# RecoveryBoard_V3.net
KiCad netlist of a schematic drawn in Altium Designer
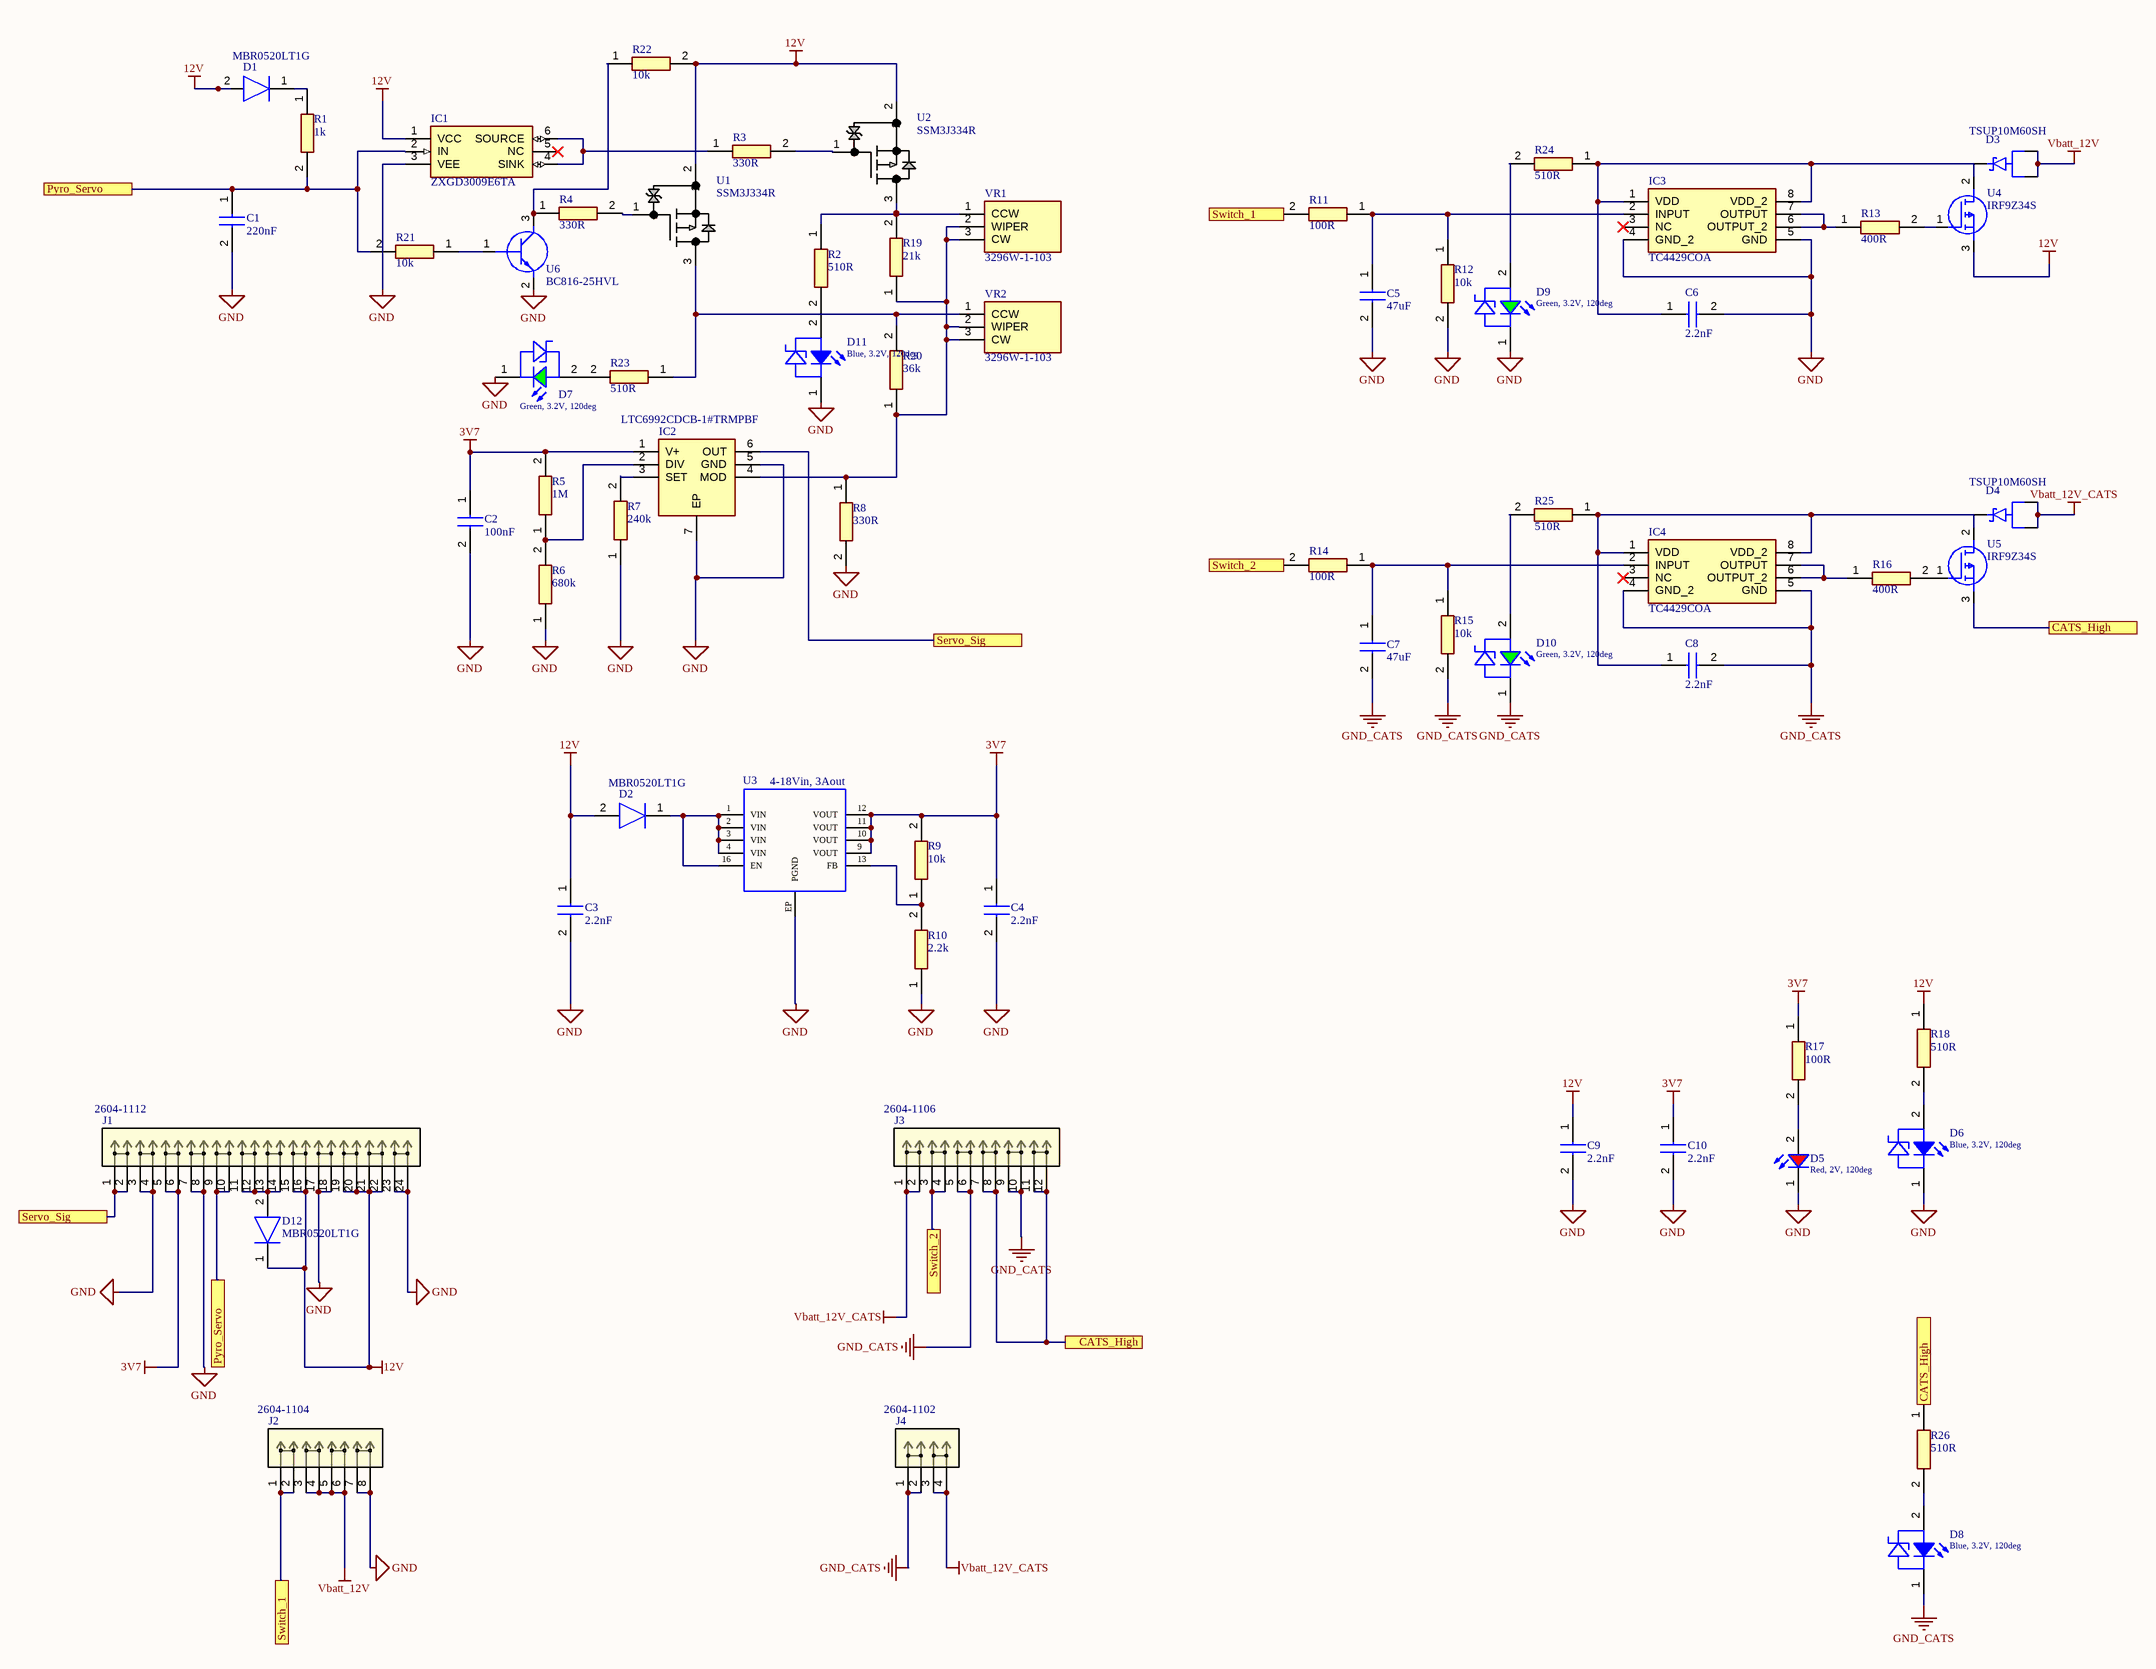
[diagram p0: RecoveryBoard_V3.SchDoc]

(export (version "E")
  (design (tool "Eeschema 10.0.6"))
  (components
    (comp (ref "C1")
      (value "220nF")
      (footprint "SamacSys:CAPC1608X87N")
      (description "Capacitor")
      (fields (field (name "MANUFACTURER_PART_NUMBER") "885012206036"))
      (libsource (lib "SamacSys") (part "885012206036"))
    )
    (comp (ref "C2")
      (value "100nF")
      (footprint "SamacSys:CAPC1608X87N")
      (description "Capacitor")
      (fields (field (name "MANUFACTURER_PART_NUMBER") "885012206036"))
      (libsource (lib "SamacSys") (part "885012206036"))
    )
    (comp (ref "C3")
      (value "2.2nF")
      (footprint "SamacSys:CAPC1608X87N")
      (description "Capacitor")
      (fields (field (name "MANUFACTURER_PART_NUMBER") "885012206036"))
      (libsource (lib "SamacSys") (part "885012206036"))
    )
    (comp (ref "C4")
      (value "2.2nF")
      (footprint "SamacSys:CAPC1608X87N")
      (description "Capacitor")
      (fields (field (name "MANUFACTURER_PART_NUMBER") "885012206036"))
      (libsource (lib "SamacSys") (part "885012206036"))
    )
    (comp (ref "C5")
      (value "47uF")
      (footprint "SamacSys:CAPC1608X87N")
      (description "Capacitor")
      (fields (field (name "MANUFACTURER_PART_NUMBER") "885012206036"))
      (libsource (lib "SamacSys") (part "885012206036"))
    )
    (comp (ref "C6")
      (value "2.2nF")
      (footprint "SamacSys:CAPC1608X87N")
      (description "Capacitor")
      (fields (field (name "MANUFACTURER_PART_NUMBER") "885012206036"))
      (libsource (lib "SamacSys") (part "885012206036"))
    )
    (comp (ref "C7")
      (value "47uF")
      (footprint "SamacSys:CAPC1608X87N")
      (description "Capacitor")
      (fields (field (name "MANUFACTURER_PART_NUMBER") "885012206036"))
      (libsource (lib "SamacSys") (part "885012206036"))
    )
    (comp (ref "C8")
      (value "2.2nF")
      (footprint "SamacSys:CAPC1608X87N")
      (description "Capacitor")
      (fields (field (name "MANUFACTURER_PART_NUMBER") "885012206036"))
      (libsource (lib "SamacSys") (part "885012206036"))
    )
    (comp (ref "C9")
      (value "2.2nF")
      (footprint "SamacSys:CAPC1608X87N")
      (description "Capacitor")
      (fields (field (name "MANUFACTURER_PART_NUMBER") "885012206036"))
      (libsource (lib "SamacSys") (part "885012206036"))
    )
    (comp (ref "C10")
      (value "2.2nF")
      (footprint "SamacSys:CAPC1608X87N")
      (description "Capacitor")
      (fields (field (name "MANUFACTURER_PART_NUMBER") "885012206036"))
      (libsource (lib "SamacSys") (part "885012206036"))
    )
    (comp (ref "D1")
      (value "MBR0520LT1G")
      (footprint "SamacSys:SOD3716X135N")
      (description "Diode")
      (libsource (lib "SamacSys") (part "MBR0520LT1G"))
    )
    (comp (ref "D2")
      (value "MBR0520LT1G")
      (footprint "SamacSys:SOD3716X135N")
      (description "Diode")
      (libsource (lib "SamacSys") (part "MBR0520LT1G"))
    )
    (comp (ref "D3")
      (value "TSUP10M60SH")
      (footprint "DIO_TSUP10M60SH")
      (libsource (lib "TSUP10M60SH") (part "TSUP10M60SH"))
    )
    (comp (ref "D4")
      (value "TSUP10M60SH")
      (footprint "DIO_TSUP10M60SH")
      (libsource (lib "TSUP10M60SH") (part "TSUP10M60SH"))
    )
    (comp (ref "D5")
      (value "Red, 2V, 120deg")
      (footprint "WL-SMCC_0603_RS_VS_YS")
      (description "WL-SMCC SMD Mono-color Chip LED Compact, size 0603, Red, 2V, 120deg")
      (fields (field (name "PART NUMBER") "150060RS73220") (field (name "PUBLISHER") "Wurth Elektronik"))
      (libsource (lib "Altium_WL-SMCC (rev19a)") (part "150060RS73220"))
    )
    (comp (ref "D6")
      (value "Blue, 3.2V, 120deg")
      (footprint "WL-SMCC_0603_GS_BS")
      (description "WL-SMCC SMD Mono-color Chip LED Compact, size 0603, Blue, 3.2V, 120deg")
      (fields (field (name "PART NUMBER") "150060BS73220") (field (name "PUBLISHER") "Wurth Elektronik"))
      (libsource (lib "Altium_WL-SMCC (rev19a)") (part "150060BS73220"))
    )
    (comp (ref "D7")
      (value "Green, 3.2V, 120deg")
      (footprint "WL-SMCC_0603_GS_BS")
      (description "WL-SMCC SMD Mono-color Chip LED Compact, size 0603, Green, 3.2V, 120deg")
      (fields (field (name "PART NUMBER") "150060GS73220") (field (name "PUBLISHER") "Wurth Elektronik"))
      (libsource (lib "Altium_WL-SMCC (rev19a)") (part "150060GS73220"))
    )
    (comp (ref "D8")
      (value "Blue, 3.2V, 120deg")
      (footprint "WL-SMCC_0603_GS_BS")
      (description "WL-SMCC SMD Mono-color Chip LED Compact, size 0603, Blue, 3.2V, 120deg")
      (fields (field (name "PART NUMBER") "150060BS73220") (field (name "PUBLISHER") "Wurth Elektronik"))
      (libsource (lib "Altium_WL-SMCC (rev19a)") (part "150060BS73220"))
    )
    (comp (ref "D9")
      (value "Green, 3.2V, 120deg")
      (footprint "WL-SMCC_0603_GS_BS")
      (description "WL-SMCC SMD Mono-color Chip LED Compact, size 0603, Green, 3.2V, 120deg")
      (fields (field (name "PART NUMBER") "150060GS73220") (field (name "PUBLISHER") "Wurth Elektronik"))
      (libsource (lib "Altium_WL-SMCC (rev19a)") (part "150060GS73220"))
    )
    (comp (ref "D10")
      (value "Green, 3.2V, 120deg")
      (footprint "WL-SMCC_0603_GS_BS")
      (description "WL-SMCC SMD Mono-color Chip LED Compact, size 0603, Green, 3.2V, 120deg")
      (fields (field (name "PART NUMBER") "150060GS73220") (field (name "PUBLISHER") "Wurth Elektronik"))
      (libsource (lib "Altium_WL-SMCC (rev19a)") (part "150060GS73220"))
    )
    (comp (ref "D11")
      (value "Blue, 3.2V, 120deg")
      (footprint "WL-SMCC_0603_GS_BS")
      (description "WL-SMCC SMD Mono-color Chip LED Compact, size 0603, Blue, 3.2V, 120deg")
      (fields (field (name "PART NUMBER") "150060BS73220") (field (name "PUBLISHER") "Wurth Elektronik"))
      (libsource (lib "Altium_WL-SMCC (rev19a)") (part "150060BS73220"))
    )
    (comp (ref "D12")
      (value "MBR0520LT1G")
      (footprint "SamacSys:SOD3716X135N")
      (description "Diode")
      (libsource (lib "SamacSys") (part "MBR0520LT1G"))
    )
    (comp (ref "IC1")
      (value "ZXGD3009E6TA")
      (footprint "SamacSys:SOT95P285X140-6N")
      (description "Integrated Circuit")
      (fields (field (name "MOUSER2 PART NUMBER") "621-ZXGD3009E6TA"))
      (libsource (lib "SamacSys") (part "ZXGD3009E6TA"))
    )
    (comp (ref "IC2")
      (value "LTC6992CDCB-1#TRMPBF")
      (footprint "SamacSys:SON50P300X200X80-7N-D")
      (description "Integrated Circuit")
      (libsource (lib "SamacSys") (part "LTC6992CDCB-1#TRMPBF"))
    )
    (comp (ref "IC3")
      (value "TC4429COA")
      (footprint "SamacSys:SOIC127P600X175-8N")
      (description "Integrated Circuit")
      (fields (field (name "MOUSER2 PART NUMBER") "579-TC4429COA"))
      (libsource (lib "SamacSys") (part "TC4429COA"))
    )
    (comp (ref "IC4")
      (value "TC4429COA")
      (footprint "SamacSys:SOIC127P600X175-8N")
      (description "Integrated Circuit")
      (fields (field (name "MOUSER2 PART NUMBER") "579-TC4429COA"))
      (libsource (lib "SamacSys") (part "TC4429COA"))
    )
    (comp (ref "J1")
      (value "2604-1112")
      (footprint "CONN_2604-1112_24_WAG")
      (description "No Description Available")
      (fields (field (name "COPYRIGHT") "Copyright (C) 2022 Ultra Librarian. All rights reserved."))
      (libsource (lib "2604-1112") (part "2604-1112"))
    )
    (comp (ref "J2")
      (value "2604-1104")
      (footprint "CONN_2604-1104_8_WAG")
      (description "No Description Available")
      (fields (field (name "COPYRIGHT") "Copyright (C) 2022 Ultra Librarian. All rights reserved."))
      (libsource (lib "2604-1104") (part "2604-1104"))
    )
    (comp (ref "J3")
      (value "2604-1106")
      (footprint "CONN_2604-1106_12_WAG")
      (description "No Description Available")
      (fields (field (name "COPYRIGHT") "Copyright (C) 2022 Ultra Librarian. All rights reserved."))
      (libsource (lib "2604-1106") (part "2604-1106"))
    )
    (comp (ref "J4")
      (value "2604-1102")
      (footprint "CONN_2604-1102_4_WAG")
      (description "No Description Available")
      (fields (field (name "COPYRIGHT") "Copyright (C) 2022 Ultra Librarian. All rights reserved."))
      (libsource (lib "2604-1102") (part "2604-1102"))
    )
    (comp (ref "R1")
      (value "1k")
      (footprint "SamacSys:RESC1608X55N")
      (description "Resistor")
      (fields (field (name "MANUFACTURER_PART_NUMBER") "SDR03EZPF1003"))
      (libsource (lib "") (part "SDR03EZPF1003_3"))
    )
    (comp (ref "R2")
      (value "510R")
      (footprint "SamacSys:RESC1608X55N")
      (description "Resistor")
      (fields (field (name "MANUFACTURER_PART_NUMBER") "SDR03EZPF1003"))
      (libsource (lib "") (part "SDR03EZPF1003_3"))
    )
    (comp (ref "R3")
      (value "330R")
      (footprint "SamacSys:RESC1608X55N")
      (description "Resistor")
      (fields (field (name "MANUFACTURER_PART_NUMBER") "SDR03EZPF1003"))
      (libsource (lib "SamacSys") (part "SDR03EZPF1003"))
    )
    (comp (ref "R4")
      (value "330R")
      (footprint "SamacSys:RESC1608X55N")
      (description "Resistor")
      (fields (field (name "MANUFACTURER_PART_NUMBER") "SDR03EZPF1003"))
      (libsource (lib "SamacSys") (part "SDR03EZPF1003"))
    )
    (comp (ref "R5")
      (value "1M")
      (footprint "SamacSys:RESC1608X55N")
      (description "Resistor")
      (fields (field (name "MANUFACTURER_PART_NUMBER") "SDR03EZPF1003"))
      (libsource (lib "") (part "SDR03EZPF1003_2"))
    )
    (comp (ref "R6")
      (value "680k")
      (footprint "SamacSys:RESC1608X55N")
      (description "Resistor")
      (fields (field (name "MANUFACTURER_PART_NUMBER") "SDR03EZPF1003"))
      (libsource (lib "") (part "SDR03EZPF1003_2"))
    )
    (comp (ref "R7")
      (value "240k")
      (footprint "SamacSys:RESC1608X55N")
      (description "Resistor")
      (fields (field (name "MANUFACTURER_PART_NUMBER") "SDR03EZPF1003"))
      (libsource (lib "") (part "SDR03EZPF1003_2"))
    )
    (comp (ref "R8")
      (value "330R")
      (footprint "SamacSys:RESC1608X55N")
      (description "Resistor")
      (fields (field (name "MANUFACTURER_PART_NUMBER") "SDR03EZPF1003"))
      (libsource (lib "") (part "SDR03EZPF1003_3"))
    )
    (comp (ref "R9")
      (value "10k")
      (footprint "SamacSys:RESC1608X55N")
      (description "Resistor")
      (fields (field (name "MANUFACTURER_PART_NUMBER") "SDR03EZPF1003"))
      (libsource (lib "") (part "SDR03EZPF1003_2"))
    )
    (comp (ref "R10")
      (value "2.2k")
      (footprint "SamacSys:RESC1608X55N")
      (description "Resistor")
      (fields (field (name "MANUFACTURER_PART_NUMBER") "SDR03EZPF1003"))
      (libsource (lib "") (part "SDR03EZPF1003_2"))
    )
    (comp (ref "R11")
      (value "100R")
      (footprint "SamacSys:RESC1608X55N")
      (description "Resistor")
      (fields (field (name "MANUFACTURER_PART_NUMBER") "SDR03EZPF1003"))
      (libsource (lib "") (part "SDR03EZPF1003_1"))
    )
    (comp (ref "R12")
      (value "10k")
      (footprint "SamacSys:RESC1608X55N")
      (description "Resistor")
      (fields (field (name "MANUFACTURER_PART_NUMBER") "SDR03EZPF1003"))
      (libsource (lib "") (part "SDR03EZPF1003_3"))
    )
    (comp (ref "R13")
      (value "400R")
      (footprint "SamacSys:RESC1608X55N")
      (description "Resistor")
      (fields (field (name "MANUFACTURER_PART_NUMBER") "SDR03EZPF1003"))
      (libsource (lib "SamacSys") (part "SDR03EZPF1003"))
    )
    (comp (ref "R14")
      (value "100R")
      (footprint "SamacSys:RESC1608X55N")
      (description "Resistor")
      (fields (field (name "MANUFACTURER_PART_NUMBER") "SDR03EZPF1003"))
      (libsource (lib "") (part "SDR03EZPF1003_1"))
    )
    (comp (ref "R15")
      (value "10k")
      (footprint "SamacSys:RESC1608X55N")
      (description "Resistor")
      (fields (field (name "MANUFACTURER_PART_NUMBER") "SDR03EZPF1003"))
      (libsource (lib "") (part "SDR03EZPF1003_3"))
    )
    (comp (ref "R16")
      (value "400R")
      (footprint "SamacSys:RESC1608X55N")
      (description "Resistor")
      (fields (field (name "MANUFACTURER_PART_NUMBER") "SDR03EZPF1003"))
      (libsource (lib "SamacSys") (part "SDR03EZPF1003"))
    )
    (comp (ref "R17")
      (value "100R")
      (footprint "SamacSys:RESC1608X55N")
      (description "Resistor")
      (fields (field (name "MANUFACTURER_PART_NUMBER") "SDR03EZPF1003"))
      (libsource (lib "") (part "SDR03EZPF1003_3"))
    )
    (comp (ref "R18")
      (value "510R")
      (footprint "SamacSys:RESC1608X55N")
      (description "Resistor")
      (fields (field (name "MANUFACTURER_PART_NUMBER") "SDR03EZPF1003"))
      (libsource (lib "") (part "SDR03EZPF1003_3"))
    )
    (comp (ref "R19")
      (value "21k")
      (footprint "SamacSys:RESC1608X55N")
      (description "Resistor")
      (fields (field (name "MANUFACTURER_PART_NUMBER") "SDR03EZPF1003"))
      (libsource (lib "") (part "SDR03EZPF1003_2"))
    )
    (comp (ref "R20")
      (value "36k")
      (footprint "SamacSys:RESC1608X55N")
      (description "Resistor")
      (fields (field (name "MANUFACTURER_PART_NUMBER") "SDR03EZPF1003"))
      (libsource (lib "") (part "SDR03EZPF1003_2"))
    )
    (comp (ref "R21")
      (value "10k")
      (footprint "SamacSys:RESC1608X55N")
      (description "Resistor")
      (fields (field (name "MANUFACTURER_PART_NUMBER") "SDR03EZPF1003"))
      (libsource (lib "") (part "SDR03EZPF1003_1"))
    )
    (comp (ref "R22")
      (value "10k")
      (footprint "SamacSys:RESC1608X55N")
      (description "Resistor")
      (fields (field (name "MANUFACTURER_PART_NUMBER") "SDR03EZPF1003"))
      (libsource (lib "SamacSys") (part "SDR03EZPF1003"))
    )
    (comp (ref "R23")
      (value "510R")
      (footprint "SamacSys:RESC1608X55N")
      (description "Resistor")
      (fields (field (name "MANUFACTURER_PART_NUMBER") "SDR03EZPF1003"))
      (libsource (lib "") (part "SDR03EZPF1003_1"))
    )
    (comp (ref "R24")
      (value "510R")
      (footprint "SamacSys:RESC1608X55N")
      (description "Resistor")
      (fields (field (name "MANUFACTURER_PART_NUMBER") "SDR03EZPF1003"))
      (libsource (lib "") (part "SDR03EZPF1003_1"))
    )
    (comp (ref "R25")
      (value "510R")
      (footprint "SamacSys:RESC1608X55N")
      (description "Resistor")
      (fields (field (name "MANUFACTURER_PART_NUMBER") "SDR03EZPF1003"))
      (libsource (lib "") (part "SDR03EZPF1003_1"))
    )
    (comp (ref "R26")
      (value "510R")
      (footprint "SamacSys:RESC1608X55N")
      (description "Resistor")
      (fields (field (name "MANUFACTURER_PART_NUMBER") "SDR03EZPF1003"))
      (libsource (lib "") (part "SDR03EZPF1003_3"))
    )
    (comp (ref "U1")
      (value "SSM3J334R")
      (footprint "SOT-23F_TOS")
      (description "No Description Available")
      (fields (field (name "COPYRIGHT") "Copyright (C) 2022 Ultra Librarian. All rights reserved."))
      (libsource (lib "SSM3J334R") (part "SSM3J334R"))
    )
    (comp (ref "U2")
      (value "SSM3J334R")
      (footprint "SOT-23F_TOS")
      (description "No Description Available")
      (fields (field (name "COPYRIGHT") "Copyright (C) 2022 Ultra Librarian. All rights reserved."))
      (libsource (lib "SSM3J334R") (part "SSM3J334R"))
    )
    (comp (ref "U3")
      (value "4-18Vin, 3Aout")
      (footprint "LGA-16EP")
      (description "MagI3C-VDRM Variable Step Down Regulator Module, LGA-16EP, 4-18Vin, 3Aout")
      (fields
        (field (name "MANUFACTURER PART NUMBER") "171031801")
        (field (name "MANUFACTURER") "Wurth Elektronik")
      )
      (libsource (lib "MagIC-VDRM (rev20a)") (part "171031801"))
    )
    (comp (ref "U4")
      (value "IRF9Z34S")
      (footprint "SamacSys:TO-263(D2PAK)")
      (description "MOSFET (P-Channel)")
      (fields (field (name "MOUSER PART NUMBER") "844-IRF9Z34S"))
      (libsource (lib "SamacSys") (part "IRF9Z34S"))
    )
    (comp (ref "U5")
      (value "IRF9Z34S")
      (footprint "SamacSys:TO-263(D2PAK)")
      (description "MOSFET (P-Channel)")
      (fields (field (name "MOUSER PART NUMBER") "844-IRF9Z34S"))
      (libsource (lib "SamacSys") (part "IRF9Z34S"))
    )
    (comp (ref "U6")
      (value "BC816-25HVL")
      (footprint "SamacSys:SOT95P230X110-3N")
      (description "Transistor BJT NPN")
      (libsource (lib "*") (part "BC816-25HVL"))
    )
    (comp (ref "VR1")
      (value "3296W-1-103")
      (footprint "SamacSys:3296W1103")
      (description "Variable Resistor")
      (fields (field (name "MOUSER PART NUMBER") "652-3296W-1-103"))
      (libsource (lib "SamacSys") (part "3296W-1-103"))
    )
    (comp (ref "VR2")
      (value "3296W-1-103")
      (footprint "SamacSys:3296W1103")
      (description "Variable Resistor")
      (fields (field (name "MOUSER PART NUMBER") "652-3296W-1-103"))
      (libsource (lib "SamacSys") (part "3296W-1-103"))
    )
  )
  (nets
    (net (code "1") (name "/CATS_High") (class "Default")
      (node (ref "J3") (pin "11") (pinfunction "11_11") (pintype "passive"))
      (node (ref "J3") (pin "12") (pinfunction "12_12") (pintype "passive"))
      (node (ref "J3") (pin "7") (pinfunction "7_7") (pintype "passive"))
      (node (ref "J3") (pin "8") (pinfunction "8_8") (pintype "passive"))
      (node (ref "R26") (pin "1") (pinfunction "1_1") (pintype "passive"))
      (node (ref "U5") (pin "3") (pinfunction "G_3") (pintype "passive"))
    )
    (net (code "2") (name "/Pyro_Servo") (class "Default")
      (node (ref "C1") (pin "1") (pinfunction "1_1") (pintype "passive"))
      (node (ref "IC1") (pin "2") (pinfunction "IN_2") (pintype "input"))
      (node (ref "J1") (pin "10") (pinfunction "10_10") (pintype "passive"))
      (node (ref "J1") (pin "9") (pinfunction "9_9") (pintype "passive"))
      (node (ref "R1") (pin "2") (pinfunction "2_2") (pintype "passive"))
      (node (ref "R21") (pin "2") (pinfunction "2_2") (pintype "passive"))
    )
    (net (code "3") (name "/Servo_Sig") (class "Default")
      (node (ref "IC2") (pin "6") (pinfunction "OUT_6") (pintype "passive"))
      (node (ref "J1") (pin "1") (pinfunction "1_1") (pintype "passive"))
      (node (ref "J1") (pin "2") (pinfunction "2_2") (pintype "passive"))
    )
    (net (code "4") (name "/Switch_1") (class "Default")
      (node (ref "J2") (pin "1") (pinfunction "1_1") (pintype "passive"))
      (node (ref "J2") (pin "2") (pinfunction "2_2") (pintype "passive"))
      (node (ref "R11") (pin "2") (pinfunction "2_2") (pintype "passive"))
    )
    (net (code "5") (name "/Switch_2") (class "Default")
      (node (ref "J3") (pin "3") (pinfunction "3_3") (pintype "passive"))
      (node (ref "J3") (pin "4") (pinfunction "4_4") (pintype "passive"))
      (node (ref "R14") (pin "2") (pinfunction "2_2") (pintype "passive"))
    )
    (net (code "6") (name "3V7") (class "Default")
      (node (ref "C10") (pin "1") (pinfunction "1_1") (pintype "passive"))
      (node (ref "C2") (pin "1") (pinfunction "1_1") (pintype "passive"))
      (node (ref "C4") (pin "1") (pinfunction "1_1") (pintype "passive"))
      (node (ref "IC2") (pin "1") (pinfunction "V+_1") (pintype "passive"))
      (node (ref "J1") (pin "5") (pinfunction "5_5") (pintype "passive"))
      (node (ref "J1") (pin "6") (pinfunction "6_6") (pintype "passive"))
      (node (ref "R17") (pin "1") (pinfunction "1_1") (pintype "passive"))
      (node (ref "R5") (pin "2") (pinfunction "2_2") (pintype "passive"))
      (node (ref "R9") (pin "2") (pinfunction "2_2") (pintype "passive"))
      (node (ref "U3") (pin "10") (pinfunction "VOUT_10") (pintype "passive"))
      (node (ref "U3") (pin "11") (pinfunction "VOUT_11") (pintype "passive"))
      (node (ref "U3") (pin "12") (pinfunction "VOUT_12") (pintype "passive"))
      (node (ref "U3") (pin "9") (pinfunction "VOUT_9") (pintype "passive"))
    )
    (net (code "7") (name "12V") (class "Default")
      (node (ref "C3") (pin "1") (pinfunction "1_1") (pintype "passive"))
      (node (ref "C9") (pin "1") (pinfunction "1_1") (pintype "passive"))
      (node (ref "D1") (pin "2") (pinfunction "A_2") (pintype "passive"))
      (node (ref "D12") (pin "1") (pinfunction "K_1") (pintype "passive"))
      (node (ref "D2") (pin "2") (pinfunction "A_2") (pintype "passive"))
      (node (ref "IC1") (pin "1") (pinfunction "VCC_1") (pintype "power_in"))
      (node (ref "J1") (pin "15") (pinfunction "15_15") (pintype "passive"))
      (node (ref "J1") (pin "16") (pinfunction "16_16") (pintype "passive"))
      (node (ref "J1") (pin "19") (pinfunction "19_19") (pintype "passive"))
      (node (ref "J1") (pin "20") (pinfunction "20_20") (pintype "passive"))
      (node (ref "J1") (pin "21") (pinfunction "21_21") (pintype "passive"))
      (node (ref "J1") (pin "22") (pinfunction "22_22") (pintype "passive"))
      (node (ref "R18") (pin "1") (pinfunction "1_1") (pintype "passive"))
      (node (ref "R22") (pin "2") (pinfunction "2_2") (pintype "passive"))
      (node (ref "U1") (pin "2") (pinfunction "2_2") (pintype "passive"))
      (node (ref "U2") (pin "2") (pinfunction "2_2") (pintype "passive"))
      (node (ref "U4") (pin "3") (pinfunction "G_3") (pintype "passive"))
    )
    (net (code "8") (name "GND") (class "Default")
      (node (ref "C1") (pin "2") (pinfunction "2_2") (pintype "passive"))
      (node (ref "C10") (pin "2") (pinfunction "2_2") (pintype "passive"))
      (node (ref "C2") (pin "2") (pinfunction "2_2") (pintype "passive"))
      (node (ref "C3") (pin "2") (pinfunction "2_2") (pintype "passive"))
      (node (ref "C4") (pin "2") (pinfunction "2_2") (pintype "passive"))
      (node (ref "C5") (pin "2") (pinfunction "2_2") (pintype "passive"))
      (node (ref "C6") (pin "2") (pinfunction "2_2") (pintype "passive"))
      (node (ref "C9") (pin "2") (pinfunction "2_2") (pintype "passive"))
      (node (ref "D11") (pin "1") (pinfunction "K_1") (pintype "passive"))
      (node (ref "D5") (pin "1") (pinfunction "K_1") (pintype "passive"))
      (node (ref "D6") (pin "1") (pinfunction "K_1") (pintype "passive"))
      (node (ref "D7") (pin "1") (pinfunction "K_1") (pintype "passive"))
      (node (ref "D9") (pin "1") (pinfunction "K_1") (pintype "passive"))
      (node (ref "IC1") (pin "3") (pinfunction "VEE_3") (pintype "power_in"))
      (node (ref "IC2") (pin "5") (pinfunction "GND_5") (pintype "passive"))
      (node (ref "IC2") (pin "7") (pinfunction "EP_7") (pintype "passive"))
      (node (ref "IC3") (pin "4") (pinfunction "GND_2_4") (pintype "passive"))
      (node (ref "IC3") (pin "5") (pinfunction "GND_5") (pintype "passive"))
      (node (ref "J1") (pin "17") (pinfunction "17_17") (pintype "passive"))
      (node (ref "J1") (pin "18") (pinfunction "18_18") (pintype "passive"))
      (node (ref "J1") (pin "23") (pinfunction "23_23") (pintype "passive"))
      (node (ref "J1") (pin "24") (pinfunction "24_24") (pintype "passive"))
      (node (ref "J1") (pin "3") (pinfunction "3_3") (pintype "passive"))
      (node (ref "J1") (pin "4") (pinfunction "4_4") (pintype "passive"))
      (node (ref "J1") (pin "7") (pinfunction "7_7") (pintype "passive"))
      (node (ref "J1") (pin "8") (pinfunction "8_8") (pintype "passive"))
      (node (ref "J2") (pin "7") (pinfunction "7_7") (pintype "passive"))
      (node (ref "J2") (pin "8") (pinfunction "8_8") (pintype "passive"))
      (node (ref "R10") (pin "1") (pinfunction "1_1") (pintype "passive"))
      (node (ref "R12") (pin "2") (pinfunction "2_2") (pintype "passive"))
      (node (ref "R6") (pin "1") (pinfunction "1_1") (pintype "passive"))
      (node (ref "R7") (pin "1") (pinfunction "1_1") (pintype "passive"))
      (node (ref "R8") (pin "2") (pinfunction "2_2") (pintype "passive"))
      (node (ref "U3") (pin "EP") (pinfunction "PGND_EP") (pintype "passive"))
      (node (ref "U6") (pin "2") (pinfunction "E_2") (pintype "passive"))
    )
    (net (code "9") (name "GND_CATS") (class "Default")
      (node (ref "C7") (pin "2") (pinfunction "2_2") (pintype "passive"))
      (node (ref "C8") (pin "2") (pinfunction "2_2") (pintype "passive"))
      (node (ref "D10") (pin "1") (pinfunction "K_1") (pintype "passive"))
      (node (ref "D8") (pin "1") (pinfunction "K_1") (pintype "passive"))
      (node (ref "IC4") (pin "4") (pinfunction "GND_2_4") (pintype "passive"))
      (node (ref "IC4") (pin "5") (pinfunction "GND_5") (pintype "passive"))
      (node (ref "J3") (pin "10") (pinfunction "10_10") (pintype "passive"))
      (node (ref "J3") (pin "5") (pinfunction "5_5") (pintype "passive"))
      (node (ref "J3") (pin "6") (pinfunction "6_6") (pintype "passive"))
      (node (ref "J3") (pin "9") (pinfunction "9_9") (pintype "passive"))
      (node (ref "J4") (pin "1") (pinfunction "1_1") (pintype "passive"))
      (node (ref "J4") (pin "2") (pinfunction "2_2") (pintype "passive"))
      (node (ref "R15") (pin "2") (pinfunction "2_2") (pintype "passive"))
    )
    (net (code "10") (name "Net-(D1-K)") (class "Default")
      (node (ref "D1") (pin "1") (pinfunction "K_1") (pintype "passive"))
      (node (ref "R1") (pin "1") (pinfunction "1_1") (pintype "passive"))
    )
    (net (code "11") (name "Net-(D2-K)") (class "Default")
      (node (ref "D2") (pin "1") (pinfunction "K_1") (pintype "passive"))
      (node (ref "U3") (pin "1") (pinfunction "VIN_1") (pintype "passive"))
      (node (ref "U3") (pin "16") (pinfunction "EN_16") (pintype "passive"))
      (node (ref "U3") (pin "2") (pinfunction "VIN_2") (pintype "passive"))
      (node (ref "U3") (pin "3") (pinfunction "VIN_3") (pintype "passive"))
      (node (ref "U3") (pin "4") (pinfunction "VIN_4") (pintype "passive"))
    )
    (net (code "12") (name "Net-(D3-K)") (class "Default")
      (node (ref "C6") (pin "1") (pinfunction "1_1") (pintype "passive"))
      (node (ref "D3") (pin "3") (pinfunction "K_3") (pintype "passive"))
      (node (ref "IC3") (pin "1") (pinfunction "VDD_1") (pintype "passive"))
      (node (ref "IC3") (pin "8") (pinfunction "VDD_2_8") (pintype "passive"))
      (node (ref "R24") (pin "1") (pinfunction "1_1") (pintype "passive"))
      (node (ref "U4") (pin "2") (pinfunction "D_2") (pintype "passive"))
    )
    (net (code "13") (name "Net-(D4-K)") (class "Default")
      (node (ref "C8") (pin "1") (pinfunction "1_1") (pintype "passive"))
      (node (ref "D4") (pin "3") (pinfunction "K_3") (pintype "passive"))
      (node (ref "IC4") (pin "1") (pinfunction "VDD_1") (pintype "passive"))
      (node (ref "IC4") (pin "8") (pinfunction "VDD_2_8") (pintype "passive"))
      (node (ref "R25") (pin "1") (pinfunction "1_1") (pintype "passive"))
      (node (ref "U5") (pin "2") (pinfunction "D_2") (pintype "passive"))
    )
    (net (code "14") (name "Net-(D5-A)") (class "Default")
      (node (ref "D5") (pin "2") (pinfunction "A_2") (pintype "passive"))
      (node (ref "R17") (pin "2") (pinfunction "2_2") (pintype "passive"))
    )
    (net (code "15") (name "Net-(D6-A)") (class "Default")
      (node (ref "D6") (pin "2") (pinfunction "A_2") (pintype "passive"))
      (node (ref "R18") (pin "2") (pinfunction "2_2") (pintype "passive"))
    )
    (net (code "16") (name "Net-(D7-A)") (class "Default")
      (node (ref "D7") (pin "2") (pinfunction "A_2") (pintype "passive"))
      (node (ref "R23") (pin "2") (pinfunction "2_2") (pintype "passive"))
    )
    (net (code "17") (name "Net-(D8-A)") (class "Default")
      (node (ref "D8") (pin "2") (pinfunction "A_2") (pintype "passive"))
      (node (ref "R26") (pin "2") (pinfunction "2_2") (pintype "passive"))
    )
    (net (code "18") (name "Net-(D9-A)") (class "Default")
      (node (ref "D9") (pin "2") (pinfunction "A_2") (pintype "passive"))
      (node (ref "R24") (pin "2") (pinfunction "2_2") (pintype "passive"))
    )
    (net (code "19") (name "Net-(D10-A)") (class "Default")
      (node (ref "D10") (pin "2") (pinfunction "A_2") (pintype "passive"))
      (node (ref "R25") (pin "2") (pinfunction "2_2") (pintype "passive"))
    )
    (net (code "20") (name "Net-(D11-A)") (class "Default")
      (node (ref "D11") (pin "2") (pinfunction "A_2") (pintype "passive"))
      (node (ref "R2") (pin "2") (pinfunction "2_2") (pintype "passive"))
    )
    (net (code "21") (name "Net-(D12-A)") (class "Default")
      (node (ref "D12") (pin "2") (pinfunction "A_2") (pintype "passive"))
      (node (ref "J1") (pin "11") (pinfunction "11_11") (pintype "passive"))
      (node (ref "J1") (pin "12") (pinfunction "12_12") (pintype "passive"))
      (node (ref "J1") (pin "13") (pinfunction "13_13") (pintype "passive"))
      (node (ref "J1") (pin "14") (pinfunction "14_14") (pintype "passive"))
    )
    (net (code "22") (name "Net-(IC1-SINK)") (class "Default")
      (node (ref "IC1") (pin "4") (pinfunction "SINK_4") (pintype "bidirectional"))
      (node (ref "IC1") (pin "6") (pinfunction "SOURCE_6") (pintype "bidirectional"))
      (node (ref "R3") (pin "1") (pinfunction "1_1") (pintype "passive"))
    )
    (net (code "23") (name "Net-(IC2-DIV)") (class "Default")
      (node (ref "IC2") (pin "2") (pinfunction "DIV_2") (pintype "passive"))
      (node (ref "R5") (pin "1") (pinfunction "1_1") (pintype "passive"))
      (node (ref "R6") (pin "2") (pinfunction "2_2") (pintype "passive"))
    )
    (net (code "24") (name "Net-(IC2-MOD)") (class "Default")
      (node (ref "IC2") (pin "4") (pinfunction "MOD_4") (pintype "passive"))
      (node (ref "R19") (pin "1") (pinfunction "1_1") (pintype "passive"))
      (node (ref "R20") (pin "1") (pinfunction "1_1") (pintype "passive"))
      (node (ref "R8") (pin "1") (pinfunction "1_1") (pintype "passive"))
      (node (ref "VR1") (pin "2") (pinfunction "WIPER_2") (pintype "passive"))
      (node (ref "VR1") (pin "3") (pinfunction "CW_3") (pintype "passive"))
      (node (ref "VR2") (pin "2") (pinfunction "WIPER_2") (pintype "passive"))
      (node (ref "VR2") (pin "3") (pinfunction "CW_3") (pintype "passive"))
    )
    (net (code "25") (name "Net-(IC2-SET)") (class "Default")
      (node (ref "IC2") (pin "3") (pinfunction "SET_3") (pintype "passive"))
      (node (ref "R7") (pin "2") (pinfunction "2_2") (pintype "passive"))
    )
    (net (code "26") (name "Net-(IC3-INPUT)") (class "Default")
      (node (ref "C5") (pin "1") (pinfunction "1_1") (pintype "passive"))
      (node (ref "IC3") (pin "2") (pinfunction "INPUT_2") (pintype "passive"))
      (node (ref "R11") (pin "1") (pinfunction "1_1") (pintype "passive"))
      (node (ref "R12") (pin "1") (pinfunction "1_1") (pintype "passive"))
    )
    (net (code "27") (name "Net-(IC3-OUTPUT)") (class "Default")
      (node (ref "IC3") (pin "6") (pinfunction "OUTPUT_2_6") (pintype "passive"))
      (node (ref "IC3") (pin "7") (pinfunction "OUTPUT_7") (pintype "passive"))
      (node (ref "R13") (pin "1") (pinfunction "1_1") (pintype "passive"))
    )
    (net (code "28") (name "Net-(IC4-INPUT)") (class "Default")
      (node (ref "C7") (pin "1") (pinfunction "1_1") (pintype "passive"))
      (node (ref "IC4") (pin "2") (pinfunction "INPUT_2") (pintype "passive"))
      (node (ref "R14") (pin "1") (pinfunction "1_1") (pintype "passive"))
      (node (ref "R15") (pin "1") (pinfunction "1_1") (pintype "passive"))
    )
    (net (code "29") (name "Net-(IC4-OUTPUT)") (class "Default")
      (node (ref "IC4") (pin "6") (pinfunction "OUTPUT_2_6") (pintype "passive"))
      (node (ref "IC4") (pin "7") (pinfunction "OUTPUT_7") (pintype "passive"))
      (node (ref "R16") (pin "1") (pinfunction "1_1") (pintype "passive"))
    )
    (net (code "30") (name "Net-(R3-Pad2)") (class "Default")
      (node (ref "R3") (pin "2") (pinfunction "2_2") (pintype "passive"))
      (node (ref "U2") (pin "1") (pinfunction "1_1") (pintype "passive"))
    )
    (net (code "31") (name "Net-(R4-Pad2)") (class "Default")
      (node (ref "R4") (pin "2") (pinfunction "2_2") (pintype "passive"))
      (node (ref "U1") (pin "1") (pinfunction "1_1") (pintype "passive"))
    )
    (net (code "32") (name "Net-(R13-Pad2)") (class "Default")
      (node (ref "R13") (pin "2") (pinfunction "2_2") (pintype "passive"))
      (node (ref "U4") (pin "1") (pinfunction "G_1") (pintype "passive"))
    )
    (net (code "33") (name "Net-(R16-Pad2)") (class "Default")
      (node (ref "R16") (pin "2") (pinfunction "2_2") (pintype "passive"))
      (node (ref "U5") (pin "1") (pinfunction "G_1") (pintype "passive"))
    )
    (net (code "34") (name "Net-(U3-FB)") (class "Default")
      (node (ref "R10") (pin "2") (pinfunction "2_2") (pintype "passive"))
      (node (ref "R9") (pin "1") (pinfunction "1_1") (pintype "passive"))
      (node (ref "U3") (pin "13") (pinfunction "FB_13") (pintype "passive"))
    )
    (net (code "35") (name "Net-(U6-B)") (class "Default")
      (node (ref "R21") (pin "1") (pinfunction "1_1") (pintype "passive"))
      (node (ref "U6") (pin "1") (pinfunction "B_1") (pintype "passive"))
    )
    (net (code "36") (name "Net-(U6-C)") (class "Default")
      (node (ref "R22") (pin "1") (pinfunction "1_1") (pintype "passive"))
      (node (ref "R4") (pin "1") (pinfunction "1_1") (pintype "passive"))
      (node (ref "U6") (pin "3") (pinfunction "C_3") (pintype "passive"))
    )
    (net (code "37") (name "Net-(VR1-CCW)") (class "Default")
      (node (ref "R19") (pin "2") (pinfunction "2_2") (pintype "passive"))
      (node (ref "R2") (pin "1") (pinfunction "1_1") (pintype "passive"))
      (node (ref "U2") (pin "3") (pinfunction "3_3") (pintype "passive"))
      (node (ref "VR1") (pin "1") (pinfunction "CCW_1") (pintype "passive"))
    )
    (net (code "38") (name "Net-(VR2-CCW)") (class "Default")
      (node (ref "R20") (pin "2") (pinfunction "2_2") (pintype "passive"))
      (node (ref "R23") (pin "1") (pinfunction "1_1") (pintype "passive"))
      (node (ref "U1") (pin "3") (pinfunction "3_3") (pintype "passive"))
      (node (ref "VR2") (pin "1") (pinfunction "CCW_1") (pintype "passive"))
    )
    (net (code "39") (name "Vbatt_12V") (class "Default")
      (node (ref "D3") (pin "1") (pinfunction "A1_1") (pintype "passive"))
      (node (ref "D3") (pin "2") (pinfunction "A2_2") (pintype "passive"))
      (node (ref "J2") (pin "3") (pinfunction "3_3") (pintype "passive"))
      (node (ref "J2") (pin "4") (pinfunction "4_4") (pintype "passive"))
      (node (ref "J2") (pin "5") (pinfunction "5_5") (pintype "passive"))
      (node (ref "J2") (pin "6") (pinfunction "6_6") (pintype "passive"))
    )
    (net (code "40") (name "Vbatt_12V_CATS") (class "Default")
      (node (ref "D4") (pin "1") (pinfunction "A1_1") (pintype "passive"))
      (node (ref "D4") (pin "2") (pinfunction "A2_2") (pintype "passive"))
      (node (ref "J3") (pin "1") (pinfunction "1_1") (pintype "passive"))
      (node (ref "J3") (pin "2") (pinfunction "2_2") (pintype "passive"))
      (node (ref "J4") (pin "3") (pinfunction "3_3") (pintype "passive"))
      (node (ref "J4") (pin "4") (pinfunction "4_4") (pintype "passive"))
    )
    (net (code "41") (name "unconnected-(IC1-NC-Pad5)") (class "Default")
      (node (ref "IC1") (pin "5") (pinfunction "NC_5") (pintype "passive+no_connect"))
    )
    (net (code "42") (name "unconnected-(IC3-NC-Pad3)") (class "Default")
      (node (ref "IC3") (pin "3") (pinfunction "NC_3") (pintype "passive+no_connect"))
    )
    (net (code "43") (name "unconnected-(IC4-NC-Pad3)") (class "Default")
      (node (ref "IC4") (pin "3") (pinfunction "NC_3") (pintype "passive+no_connect"))
    )
  )
)
